# 2313tmpcontroller.net
KiCad netlist of a schematic drawn in EAGLE
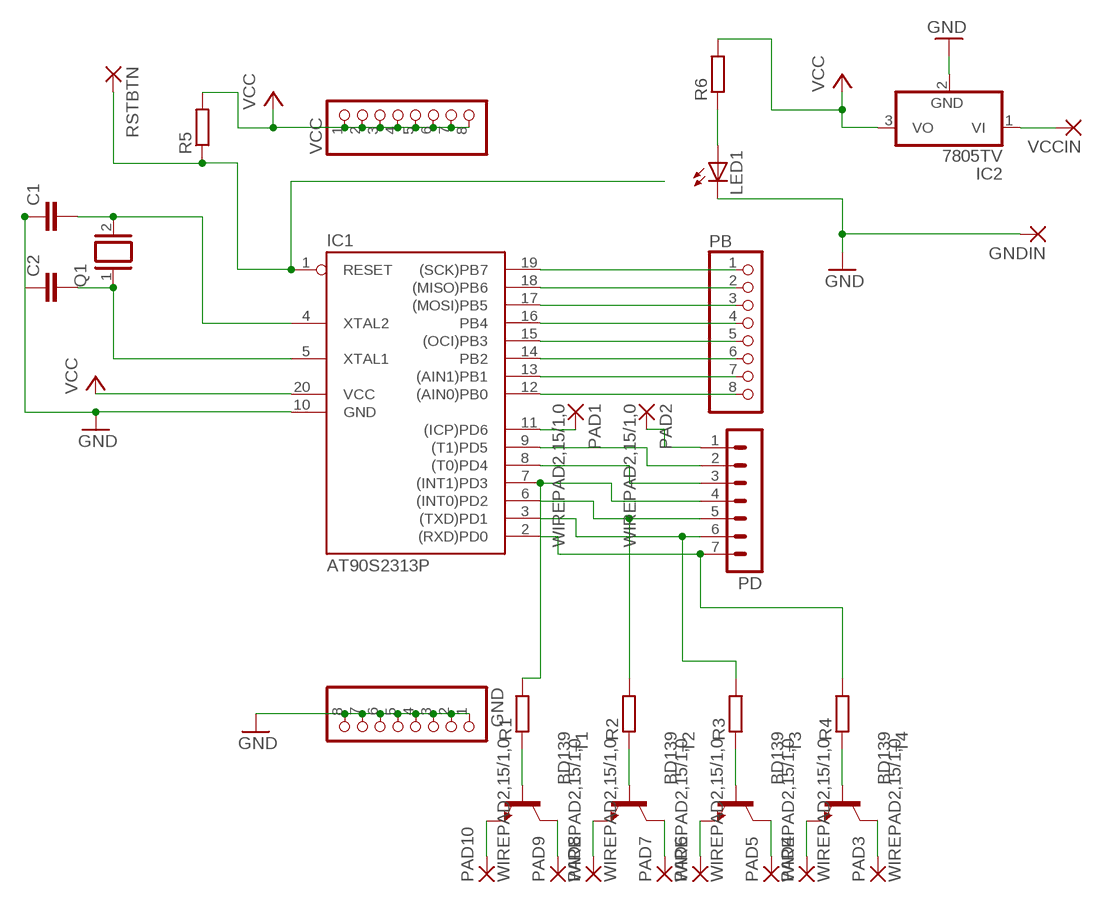
[diagram p0: schematic, sheet 1]

(export (version "E")
  (design (tool "Eeschema 10.0.6"))
  (components
    (comp (ref "C1")
      (value "C2,5-3")
      (footprint "eagle-import:C2.5-3")
      (libsource (lib "eagle-import") (part "C2,5-3"))
    )
    (comp (ref "C2")
      (value "C2,5-3")
      (footprint "eagle-import:C2.5-3")
      (libsource (lib "eagle-import") (part "C2,5-3"))
    )
    (comp (ref "GND")
      (value "PINHD-1X8")
      (footprint "eagle-import:1X08")
      (libsource (lib "eagle-import") (part "PINHD-1X8"))
    )
    (comp (ref "GNDIN")
      (value "2,54/0,8")
      (footprint "eagle-import:2,54_0,8")
      (libsource (lib "eagle-import") (part "2,54/0,8"))
    )
    (comp (ref "IC1")
      (value "AT90S2313P")
      (footprint "eagle-import:DIL20")
      (libsource (lib "eagle-import") (part "AT90S2313P"))
    )
    (comp (ref "IC2")
      (value "7805TV")
      (footprint "eagle-import:TO220V")
      (libsource (lib "eagle-import") (part "78TV05"))
    )
    (comp (ref "LED1")
      (value "LEDB153")
      (footprint "eagle-import:Q62902-B153")
      (libsource (lib "eagle-import") (part "LEDB153"))
    )
    (comp (ref "PAD1")
      (value "WIREPAD2,15/1,0")
      (footprint "eagle-import:2,15_1,0")
      (libsource (lib "eagle-import") (part "WIREPAD2,15/1,0"))
    )
    (comp (ref "PAD2")
      (value "WIREPAD2,15/1,0")
      (footprint "eagle-import:2,15_1,0")
      (libsource (lib "eagle-import") (part "WIREPAD2,15/1,0"))
    )
    (comp (ref "PAD3")
      (value "WIREPAD2,15/1,0")
      (footprint "eagle-import:2,15_1,0")
      (libsource (lib "eagle-import") (part "WIREPAD2,15/1,0"))
    )
    (comp (ref "PAD4")
      (value "WIREPAD2,15/1,0")
      (footprint "eagle-import:2,15_1,0")
      (libsource (lib "eagle-import") (part "WIREPAD2,15/1,0"))
    )
    (comp (ref "PAD5")
      (value "WIREPAD2,15/1,0")
      (footprint "eagle-import:2,15_1,0")
      (libsource (lib "eagle-import") (part "WIREPAD2,15/1,0"))
    )
    (comp (ref "PAD6")
      (value "WIREPAD2,15/1,0")
      (footprint "eagle-import:2,15_1,0")
      (libsource (lib "eagle-import") (part "WIREPAD2,15/1,0"))
    )
    (comp (ref "PAD7")
      (value "WIREPAD2,15/1,0")
      (footprint "eagle-import:2,15_1,0")
      (libsource (lib "eagle-import") (part "WIREPAD2,15/1,0"))
    )
    (comp (ref "PAD8")
      (value "WIREPAD2,15/1,0")
      (footprint "eagle-import:2,15_1,0")
      (libsource (lib "eagle-import") (part "WIREPAD2,15/1,0"))
    )
    (comp (ref "PAD9")
      (value "WIREPAD2,15/1,0")
      (footprint "eagle-import:2,15_1,0")
      (libsource (lib "eagle-import") (part "WIREPAD2,15/1,0"))
    )
    (comp (ref "PAD10")
      (value "WIREPAD2,15/1,0")
      (footprint "eagle-import:2,15_1,0")
      (libsource (lib "eagle-import") (part "WIREPAD2,15/1,0"))
    )
    (comp (ref "PB")
      (value "PINHD-1X8")
      (footprint "eagle-import:1X08")
      (libsource (lib "eagle-import") (part "PINHD-1X8"))
    )
    (comp (ref "PD")
      (value "MA07-1")
      (footprint "eagle-import:MA07-1")
      (libsource (lib "eagle-import") (part "MA07-1"))
    )
    (comp (ref "Q1")
      (value "XTAL/S")
      (footprint "eagle-import:QS")
      (libsource (lib "eagle-import") (part "XTAL/S"))
    )
    (comp (ref "R1")
      (value "R-EU_0207/7")
      (footprint "eagle-import:0207_7")
      (libsource (lib "eagle-import") (part "R-EU_0207/7"))
    )
    (comp (ref "R2")
      (value "R-EU_0207/7")
      (footprint "eagle-import:0207_7")
      (libsource (lib "eagle-import") (part "R-EU_0207/7"))
    )
    (comp (ref "R3")
      (value "R-EU_0207/7")
      (footprint "eagle-import:0207_7")
      (libsource (lib "eagle-import") (part "R-EU_0207/7"))
    )
    (comp (ref "R4")
      (value "R-EU_0207/7")
      (footprint "eagle-import:0207_7")
      (libsource (lib "eagle-import") (part "R-EU_0207/7"))
    )
    (comp (ref "R5")
      (value "R-EU_0207/7")
      (footprint "eagle-import:0207_7")
      (libsource (lib "eagle-import") (part "R-EU_0207/7"))
    )
    (comp (ref "R6")
      (value "R-EU_0207/7")
      (footprint "eagle-import:0207_7")
      (libsource (lib "eagle-import") (part "R-EU_0207/7"))
    )
    (comp (ref "RSTBTN")
      (value "2,54/0,8")
      (footprint "eagle-import:2,54_0,8")
      (libsource (lib "eagle-import") (part "2,54/0,8"))
    )
    (comp (ref "T1")
      (value "BD139")
      (footprint "eagle-import:TO126")
      (libsource (lib "eagle-import") (part "BD139"))
    )
    (comp (ref "T2")
      (value "BD139")
      (footprint "eagle-import:TO126")
      (libsource (lib "eagle-import") (part "BD139"))
    )
    (comp (ref "T3")
      (value "BD139")
      (footprint "eagle-import:TO126")
      (libsource (lib "eagle-import") (part "BD139"))
    )
    (comp (ref "T4")
      (value "BD139")
      (footprint "eagle-import:TO126")
      (libsource (lib "eagle-import") (part "BD139"))
    )
    (comp (ref "VCC")
      (value "PINHD-1X8")
      (footprint "eagle-import:1X08")
      (libsource (lib "eagle-import") (part "PINHD-1X8"))
    )
    (comp (ref "VCCIN")
      (value "2,54/0,8")
      (footprint "eagle-import:2,54_0,8")
      (libsource (lib "eagle-import") (part "2,54/0,8"))
    )
  )
  (nets
    (net (code "1") (name "GND") (class "Default")
      (node (ref "C1") (pin "1") (pinfunction "1_1") (pintype "passive"))
      (node (ref "C2") (pin "1") (pinfunction "1_1") (pintype "passive"))
      (node (ref "GND") (pin "1") (pinfunction "1_1") (pintype "passive"))
      (node (ref "GND") (pin "2") (pinfunction "2_2") (pintype "passive"))
      (node (ref "GND") (pin "3") (pinfunction "3_3") (pintype "passive"))
      (node (ref "GND") (pin "4") (pinfunction "4_4") (pintype "passive"))
      (node (ref "GND") (pin "5") (pinfunction "5_5") (pintype "passive"))
      (node (ref "GND") (pin "6") (pinfunction "6_6") (pintype "passive"))
      (node (ref "GND") (pin "7") (pinfunction "7_7") (pintype "passive"))
      (node (ref "GND") (pin "8") (pinfunction "8_8") (pintype "passive"))
      (node (ref "GNDIN") (pin "1") (pinfunction "P_1") (pintype "passive"))
      (node (ref "IC1") (pin "10") (pinfunction "GND_10") (pintype "power_in"))
      (node (ref "IC2") (pin "2") (pinfunction "GND_2") (pintype "passive"))
      (node (ref "LED1") (pin "K") (pinfunction "C_K") (pintype "passive"))
    )
    (net (code "2") (name "Net-(IC1-(AIN0)PB0)") (class "Default")
      (node (ref "IC1") (pin "12") (pinfunction "(AIN0)PB0_12") (pintype "bidirectional"))
      (node (ref "PB") (pin "8") (pinfunction "8_8") (pintype "passive"))
    )
    (net (code "3") (name "Net-(IC1-(AIN1)PB1)") (class "Default")
      (node (ref "IC1") (pin "13") (pinfunction "(AIN1)PB1_13") (pintype "bidirectional"))
      (node (ref "PB") (pin "7") (pinfunction "7_7") (pintype "passive"))
    )
    (net (code "4") (name "Net-(IC1-(ICP)PD6)") (class "Default")
      (node (ref "IC1") (pin "11") (pinfunction "(ICP)PD6_11") (pintype "bidirectional"))
      (node (ref "PAD1") (pin "1") (pinfunction "P_1") (pintype "passive"))
    )
    (net (code "5") (name "Net-(IC1-(INT0)PD2)") (class "Default")
      (node (ref "IC1") (pin "6") (pinfunction "(INT0)PD2_6") (pintype "bidirectional"))
      (node (ref "PD") (pin "5") (pinfunction "5_5") (pintype "passive"))
      (node (ref "R2") (pin "2") (pinfunction "2_2") (pintype "passive"))
    )
    (net (code "6") (name "Net-(IC1-(INT1)PD3)") (class "Default")
      (node (ref "IC1") (pin "7") (pinfunction "(INT1)PD3_7") (pintype "bidirectional"))
      (node (ref "PD") (pin "4") (pinfunction "4_4") (pintype "passive"))
      (node (ref "R1") (pin "2") (pinfunction "2_2") (pintype "passive"))
    )
    (net (code "7") (name "Net-(IC1-(MISO)PB6)") (class "Default")
      (node (ref "IC1") (pin "18") (pinfunction "(MISO)PB6_18") (pintype "bidirectional"))
      (node (ref "PB") (pin "2") (pinfunction "2_2") (pintype "passive"))
    )
    (net (code "8") (name "Net-(IC1-(MOSI)PB5)") (class "Default")
      (node (ref "IC1") (pin "17") (pinfunction "(MOSI)PB5_17") (pintype "bidirectional"))
      (node (ref "PB") (pin "3") (pinfunction "3_3") (pintype "passive"))
    )
    (net (code "9") (name "Net-(IC1-(OCI)PB3)") (class "Default")
      (node (ref "IC1") (pin "15") (pinfunction "(OCI)PB3_15") (pintype "bidirectional"))
      (node (ref "PB") (pin "5") (pinfunction "5_5") (pintype "passive"))
    )
    (net (code "10") (name "Net-(IC1-(RXD)PD0)") (class "Default")
      (node (ref "IC1") (pin "2") (pinfunction "(RXD)PD0_2") (pintype "bidirectional"))
      (node (ref "PD") (pin "7") (pinfunction "7_7") (pintype "passive"))
      (node (ref "R4") (pin "2") (pinfunction "2_2") (pintype "passive"))
    )
    (net (code "11") (name "Net-(IC1-(SCK)PB7)") (class "Default")
      (node (ref "IC1") (pin "19") (pinfunction "(SCK)PB7_19") (pintype "bidirectional"))
      (node (ref "PB") (pin "1") (pinfunction "1_1") (pintype "passive"))
    )
    (net (code "12") (name "Net-(IC1-(T0)PD4)") (class "Default")
      (node (ref "IC1") (pin "8") (pinfunction "(T0)PD4_8") (pintype "bidirectional"))
      (node (ref "PD") (pin "3") (pinfunction "3_3") (pintype "passive"))
    )
    (net (code "13") (name "Net-(IC1-(T1)PD5)") (class "Default")
      (node (ref "IC1") (pin "9") (pinfunction "(T1)PD5_9") (pintype "bidirectional"))
      (node (ref "PD") (pin "2") (pinfunction "2_2") (pintype "passive"))
    )
    (net (code "14") (name "Net-(IC1-(TXD)PD1)") (class "Default")
      (node (ref "IC1") (pin "3") (pinfunction "(TXD)PD1_3") (pintype "bidirectional"))
      (node (ref "PD") (pin "6") (pinfunction "6_6") (pintype "passive"))
      (node (ref "R3") (pin "2") (pinfunction "2_2") (pintype "passive"))
    )
    (net (code "15") (name "Net-(IC1-PB2)") (class "Default")
      (node (ref "IC1") (pin "14") (pinfunction "PB2_14") (pintype "bidirectional"))
      (node (ref "PB") (pin "6") (pinfunction "6_6") (pintype "passive"))
    )
    (net (code "16") (name "Net-(IC1-PB4)") (class "Default")
      (node (ref "IC1") (pin "16") (pinfunction "PB4_16") (pintype "bidirectional"))
      (node (ref "PB") (pin "4") (pinfunction "4_4") (pintype "passive"))
    )
    (net (code "17") (name "Net-(IC1-RESET)") (class "Default")
      (node (ref "IC1") (pin "1") (pinfunction "RESET_1") (pintype "bidirectional"))
      (node (ref "R5") (pin "1") (pinfunction "1_1") (pintype "passive"))
      (node (ref "RSTBTN") (pin "1") (pinfunction "P_1") (pintype "passive"))
    )
    (net (code "18") (name "Net-(IC1-XTAL1)") (class "Default")
      (node (ref "C2") (pin "2") (pinfunction "2_2") (pintype "passive"))
      (node (ref "IC1") (pin "5") (pinfunction "XTAL1_5") (pintype "bidirectional"))
      (node (ref "Q1") (pin "1") (pinfunction "1_1") (pintype "passive"))
    )
    (net (code "19") (name "Net-(IC1-XTAL2)") (class "Default")
      (node (ref "C1") (pin "2") (pinfunction "2_2") (pintype "passive"))
      (node (ref "IC1") (pin "4") (pinfunction "XTAL2_4") (pintype "bidirectional"))
      (node (ref "Q1") (pin "2") (pinfunction "2_2") (pintype "passive"))
    )
    (net (code "20") (name "Net-(IC2-VI)") (class "Default")
      (node (ref "IC2") (pin "1") (pinfunction "VI_1") (pintype "input"))
      (node (ref "VCCIN") (pin "1") (pinfunction "P_1") (pintype "passive"))
    )
    (net (code "21") (name "Net-(LED1-PadA)") (class "Default")
      (node (ref "LED1") (pin "A") (pinfunction "A_A") (pintype "passive"))
      (node (ref "R6") (pin "1") (pinfunction "1_1") (pintype "passive"))
    )
    (net (code "22") (name "Net-(PAD2-P)") (class "Default")
      (node (ref "PAD2") (pin "1") (pinfunction "P_1") (pintype "passive"))
      (node (ref "PD") (pin "1") (pinfunction "1_1") (pintype "passive"))
    )
    (net (code "23") (name "Net-(PAD3-P)") (class "Default")
      (node (ref "PAD3") (pin "1") (pinfunction "P_1") (pintype "passive"))
      (node (ref "T4") (pin "2") (pinfunction "C_2") (pintype "passive"))
    )
    (net (code "24") (name "Net-(PAD4-P)") (class "Default")
      (node (ref "PAD4") (pin "1") (pinfunction "P_1") (pintype "passive"))
      (node (ref "T4") (pin "1") (pinfunction "E_1") (pintype "passive"))
    )
    (net (code "25") (name "Net-(PAD5-P)") (class "Default")
      (node (ref "PAD5") (pin "1") (pinfunction "P_1") (pintype "passive"))
      (node (ref "T3") (pin "2") (pinfunction "C_2") (pintype "passive"))
    )
    (net (code "26") (name "Net-(PAD6-P)") (class "Default")
      (node (ref "PAD6") (pin "1") (pinfunction "P_1") (pintype "passive"))
      (node (ref "T3") (pin "1") (pinfunction "E_1") (pintype "passive"))
    )
    (net (code "27") (name "Net-(PAD7-P)") (class "Default")
      (node (ref "PAD7") (pin "1") (pinfunction "P_1") (pintype "passive"))
      (node (ref "T2") (pin "2") (pinfunction "C_2") (pintype "passive"))
    )
    (net (code "28") (name "Net-(PAD8-P)") (class "Default")
      (node (ref "PAD8") (pin "1") (pinfunction "P_1") (pintype "passive"))
      (node (ref "T2") (pin "1") (pinfunction "E_1") (pintype "passive"))
    )
    (net (code "29") (name "Net-(PAD9-P)") (class "Default")
      (node (ref "PAD9") (pin "1") (pinfunction "P_1") (pintype "passive"))
      (node (ref "T1") (pin "2") (pinfunction "C_2") (pintype "passive"))
    )
    (net (code "30") (name "Net-(PAD10-P)") (class "Default")
      (node (ref "PAD10") (pin "1") (pinfunction "P_1") (pintype "passive"))
      (node (ref "T1") (pin "1") (pinfunction "E_1") (pintype "passive"))
    )
    (net (code "31") (name "Net-(T1-B)") (class "Default")
      (node (ref "R1") (pin "1") (pinfunction "1_1") (pintype "passive"))
      (node (ref "T1") (pin "3") (pinfunction "B_3") (pintype "passive"))
    )
    (net (code "32") (name "Net-(T2-B)") (class "Default")
      (node (ref "R2") (pin "1") (pinfunction "1_1") (pintype "passive"))
      (node (ref "T2") (pin "3") (pinfunction "B_3") (pintype "passive"))
    )
    (net (code "33") (name "Net-(T3-B)") (class "Default")
      (node (ref "R3") (pin "1") (pinfunction "1_1") (pintype "passive"))
      (node (ref "T3") (pin "3") (pinfunction "B_3") (pintype "passive"))
    )
    (net (code "34") (name "Net-(T4-B)") (class "Default")
      (node (ref "R4") (pin "1") (pinfunction "1_1") (pintype "passive"))
      (node (ref "T4") (pin "3") (pinfunction "B_3") (pintype "passive"))
    )
    (net (code "35") (name "VCC") (class "Default")
      (node (ref "IC1") (pin "20") (pinfunction "VCC_20") (pintype "power_in"))
      (node (ref "IC2") (pin "3") (pinfunction "VO_3") (pintype "passive"))
      (node (ref "R5") (pin "2") (pinfunction "2_2") (pintype "passive"))
      (node (ref "R6") (pin "2") (pinfunction "2_2") (pintype "passive"))
      (node (ref "VCC") (pin "1") (pinfunction "1_1") (pintype "passive"))
      (node (ref "VCC") (pin "2") (pinfunction "2_2") (pintype "passive"))
      (node (ref "VCC") (pin "3") (pinfunction "3_3") (pintype "passive"))
      (node (ref "VCC") (pin "4") (pinfunction "4_4") (pintype "passive"))
      (node (ref "VCC") (pin "5") (pinfunction "5_5") (pintype "passive"))
      (node (ref "VCC") (pin "6") (pinfunction "6_6") (pintype "passive"))
      (node (ref "VCC") (pin "7") (pinfunction "7_7") (pintype "passive"))
      (node (ref "VCC") (pin "8") (pinfunction "8_8") (pintype "passive"))
    )
  )
)
